# mice_poke_simple_v1_3.net
KiCad netlist of a schematic drawn in EAGLE
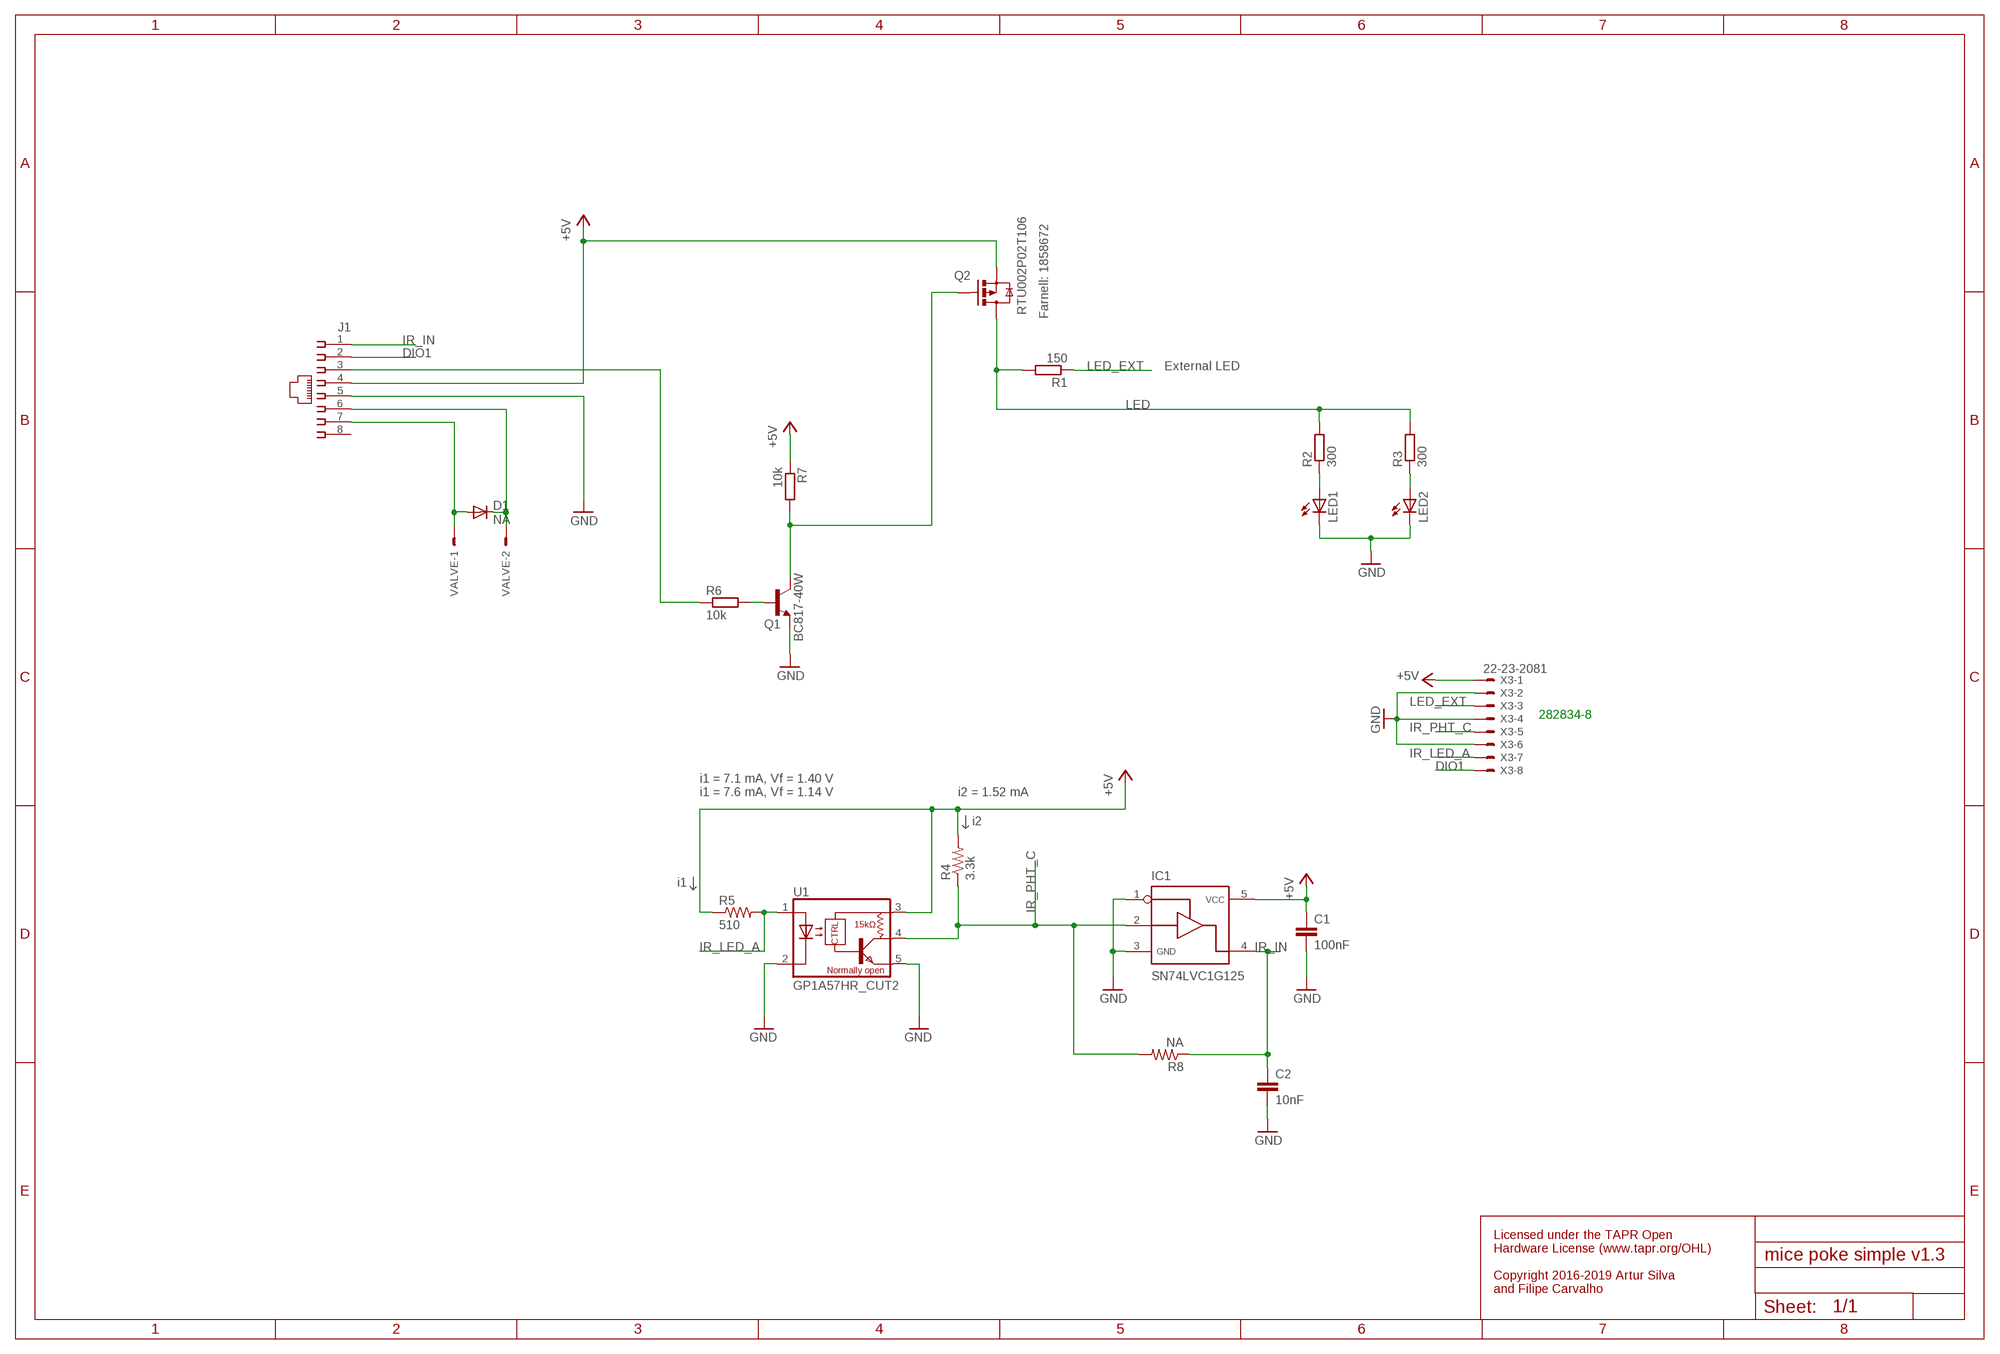
[diagram p0: schematic, sheet 1]

(export (version "E")
  (design (tool "Eeschema 10.0.6"))
  (components
    (comp (ref "C1")
      (value "100nF")
      (footprint "eagle-import:C0402")
      (libsource (lib "eagle-import") (part "C-EUC0402"))
    )
    (comp (ref "C2")
      (value "10nF")
      (footprint "eagle-import:C0402")
      (libsource (lib "eagle-import") (part "C-EUC0402"))
    )
    (comp (ref "D1")
      (value "NA")
      (footprint "eagle-import:SOD323-R")
      (libsource (lib "eagle-import") (part "DIODE-SOD323-R"))
    )
    (comp (ref "IC1")
      (value "SN74LVC1G125")
      (footprint "eagle-import:SOT23-5")
      (libsource (lib "eagle-import") (part "SN74LVC1G125"))
    )
    (comp (ref "J1")
      (value "215878-2")
      (footprint "eagle-import:215878-2")
      (libsource (lib "eagle-import") (part "215878-2"))
    )
    (comp (ref "LED1")
      (value "LED3MM")
      (footprint "eagle-import:LED3MM")
      (libsource (lib "eagle-import") (part "LED3MM"))
    )
    (comp (ref "LED2")
      (value "LED3MM")
      (footprint "eagle-import:LED3MM")
      (libsource (lib "eagle-import") (part "LED3MM"))
    )
    (comp (ref "Q1")
      (value "BC817-40W")
      (footprint "eagle-import:SOT323-BEC")
      (libsource (lib "eagle-import") (part "BC817"))
    )
    (comp (ref "Q2")
      (value "RTU002P02T106")
      (footprint "eagle-import:SOT323")
      (libsource (lib "eagle-import") (part "MOSFET-PCHANNEL-ROHM"))
    )
    (comp (ref "R1")
      (value "150")
      (footprint "eagle-import:R0402")
      (libsource (lib "eagle-import") (part "R-EU_R0402"))
    )
    (comp (ref "R2")
      (value "300")
      (footprint "eagle-import:R0402")
      (libsource (lib "eagle-import") (part "R-EU_R0402"))
    )
    (comp (ref "R3")
      (value "300")
      (footprint "eagle-import:R0402")
      (libsource (lib "eagle-import") (part "R-EU_R0402"))
    )
    (comp (ref "R4")
      (value "3.3k")
      (footprint "eagle-import:R0402")
      (libsource (lib "eagle-import") (part "R-US_R0402"))
    )
    (comp (ref "R5")
      (value "510")
      (footprint "eagle-import:R0402")
      (libsource (lib "eagle-import") (part "R-US_R0402"))
    )
    (comp (ref "R6")
      (value "10k")
      (footprint "eagle-import:R0402")
      (libsource (lib "eagle-import") (part "R-EU_R0402"))
    )
    (comp (ref "R7")
      (value "10k")
      (footprint "eagle-import:R0402")
      (libsource (lib "eagle-import") (part "R-EU_R0402"))
    )
    (comp (ref "R8")
      (value "NA")
      (footprint "eagle-import:R0402")
      (libsource (lib "eagle-import") (part "R-US_R0402"))
    )
    (comp (ref "U1")
      (value "GP1A57HR_CUT2")
      (footprint "eagle-import:GP1A57HR_CUT2")
      (libsource (lib "eagle-import") (part "GP1A57HR_CUT2"))
    )
    (comp (ref "VALVE")
      (value "22-23-2021")
      (footprint "eagle-import:22-23-2021")
      (fields (field (name "MF") "MOLEX"))
      (libsource (lib "eagle-import") (part "22-23-2021"))
    )
    (comp (ref "X3")
      (value "22-23-2081")
      (footprint "eagle-import:22-23-2081")
      (fields (field (name "MF") "MOLEX"))
      (libsource (lib "eagle-import") (part "22-23-2081"))
    )
  )
  (nets
    (net (code "1") (name "+5V") (class "Default")
      (node (ref "C1") (pin "1") (pinfunction "1_1") (pintype "passive"))
      (node (ref "IC1") (pin "5") (pinfunction "P$5_5") (pintype "bidirectional"))
      (node (ref "J1") (pin "4") (pinfunction "4_4") (pintype "passive"))
      (node (ref "Q2") (pin "1") (pinfunction "S_1") (pintype "passive"))
      (node (ref "R4") (pin "2") (pinfunction "2_2") (pintype "passive"))
      (node (ref "R5") (pin "1") (pinfunction "1_1") (pintype "passive"))
      (node (ref "R7") (pin "1") (pinfunction "1_1") (pintype "passive"))
      (node (ref "U1") (pin "3") (pinfunction "VCC_3") (pintype "passive"))
      (node (ref "X3") (pin "1") (pinfunction "S_1") (pintype "passive"))
    )
    (net (code "2") (name "/DIO1") (class "Default")
      (node (ref "J1") (pin "2") (pinfunction "2_2") (pintype "passive"))
      (node (ref "X3") (pin "8") (pinfunction "S_8") (pintype "passive"))
    )
    (net (code "3") (name "/IR_IN") (class "Default")
      (node (ref "C2") (pin "1") (pinfunction "1_1") (pintype "passive"))
      (node (ref "IC1") (pin "4") (pinfunction "P$4_4") (pintype "bidirectional"))
      (node (ref "J1") (pin "1") (pinfunction "1_1") (pintype "passive"))
      (node (ref "R8") (pin "1") (pinfunction "1_1") (pintype "passive"))
    )
    (net (code "4") (name "/IR_LED_A") (class "Default")
      (node (ref "R5") (pin "2") (pinfunction "2_2") (pintype "passive"))
      (node (ref "U1") (pin "1") (pinfunction "A_1") (pintype "passive"))
      (node (ref "X3") (pin "7") (pinfunction "S_7") (pintype "passive"))
    )
    (net (code "5") (name "/IR_PHT_C") (class "Default")
      (node (ref "IC1") (pin "2") (pinfunction "P$2_2") (pintype "bidirectional"))
      (node (ref "R4") (pin "1") (pinfunction "1_1") (pintype "passive"))
      (node (ref "R8") (pin "2") (pinfunction "2_2") (pintype "passive"))
      (node (ref "U1") (pin "4") (pinfunction "VO_4") (pintype "passive"))
      (node (ref "X3") (pin "5") (pinfunction "S_5") (pintype "passive"))
    )
    (net (code "6") (name "/LED") (class "Default")
      (node (ref "Q2") (pin "3") (pinfunction "D_3") (pintype "passive"))
      (node (ref "R1") (pin "2") (pinfunction "2_2") (pintype "passive"))
      (node (ref "R2") (pin "2") (pinfunction "2_2") (pintype "passive"))
      (node (ref "R3") (pin "2") (pinfunction "2_2") (pintype "passive"))
    )
    (net (code "7") (name "/LED_EXT") (class "Default")
      (node (ref "R1") (pin "1") (pinfunction "1_1") (pintype "passive"))
      (node (ref "X3") (pin "3") (pinfunction "S_3") (pintype "passive"))
    )
    (net (code "8") (name "GND") (class "Default")
      (node (ref "C1") (pin "2") (pinfunction "2_2") (pintype "passive"))
      (node (ref "C2") (pin "2") (pinfunction "2_2") (pintype "passive"))
      (node (ref "IC1") (pin "1") (pinfunction "P$1_1") (pintype "bidirectional"))
      (node (ref "IC1") (pin "3") (pinfunction "P$3_3") (pintype "bidirectional"))
      (node (ref "J1") (pin "5") (pinfunction "5_5") (pintype "passive"))
      (node (ref "LED1") (pin "K") (pinfunction "C_K") (pintype "passive"))
      (node (ref "LED2") (pin "K") (pinfunction "C_K") (pintype "passive"))
      (node (ref "Q1") (pin "E") (pinfunction "E_E") (pintype "passive"))
      (node (ref "U1") (pin "2") (pinfunction "C_2") (pintype "passive"))
      (node (ref "U1") (pin "5") (pinfunction "GND_5") (pintype "passive"))
      (node (ref "X3") (pin "2") (pinfunction "S_2") (pintype "passive"))
      (node (ref "X3") (pin "4") (pinfunction "S_4") (pintype "passive"))
      (node (ref "X3") (pin "6") (pinfunction "S_6") (pintype "passive"))
    )
    (net (code "9") (name "Net-(J1-Pad3)") (class "Default")
      (node (ref "J1") (pin "3") (pinfunction "3_3") (pintype "passive"))
      (node (ref "R6") (pin "1") (pinfunction "1_1") (pintype "passive"))
    )
    (net (code "10") (name "Net-(LED1-PadA)") (class "Default")
      (node (ref "LED1") (pin "A") (pinfunction "A_A") (pintype "passive"))
      (node (ref "R2") (pin "1") (pinfunction "1_1") (pintype "passive"))
    )
    (net (code "11") (name "Net-(LED2-PadA)") (class "Default")
      (node (ref "LED2") (pin "A") (pinfunction "A_A") (pintype "passive"))
      (node (ref "R3") (pin "1") (pinfunction "1_1") (pintype "passive"))
    )
    (net (code "12") (name "Net-(Q1-PadB)") (class "Default")
      (node (ref "Q1") (pin "B") (pinfunction "B_B") (pintype "passive"))
      (node (ref "R6") (pin "2") (pinfunction "2_2") (pintype "passive"))
    )
    (net (code "13") (name "Net-(Q2-G)") (class "Default")
      (node (ref "Q1") (pin "C") (pinfunction "C_C") (pintype "passive"))
      (node (ref "Q2") (pin "2") (pinfunction "G_2") (pintype "passive"))
      (node (ref "R7") (pin "2") (pinfunction "2_2") (pintype "passive"))
    )
    (net (code "14") (name "Net-(VALVEA-S)") (class "Default")
      (node (ref "D1") (pin "A") (pinfunction "A_A") (pintype "passive"))
      (node (ref "J1") (pin "7") (pinfunction "7_7") (pintype "passive"))
      (node (ref "VALVE") (pin "1") (pinfunction "S_1") (pintype "passive"))
    )
    (net (code "15") (name "Net-(VALVEB-S)") (class "Default")
      (node (ref "D1") (pin "C") (pinfunction "C_C") (pintype "passive"))
      (node (ref "J1") (pin "6") (pinfunction "6_6") (pintype "passive"))
      (node (ref "VALVE") (pin "2") (pinfunction "S_2") (pintype "passive"))
    )
    (net (code "16") (name "unconnected-(J1-Pad8)") (class "Default")
      (node (ref "J1") (pin "8") (pinfunction "8_8") (pintype "passive"))
    )
  )
)
